# chlorophyll_analyzer_spectorometer.net
KiCad netlist of a schematic drawn in EAGLE
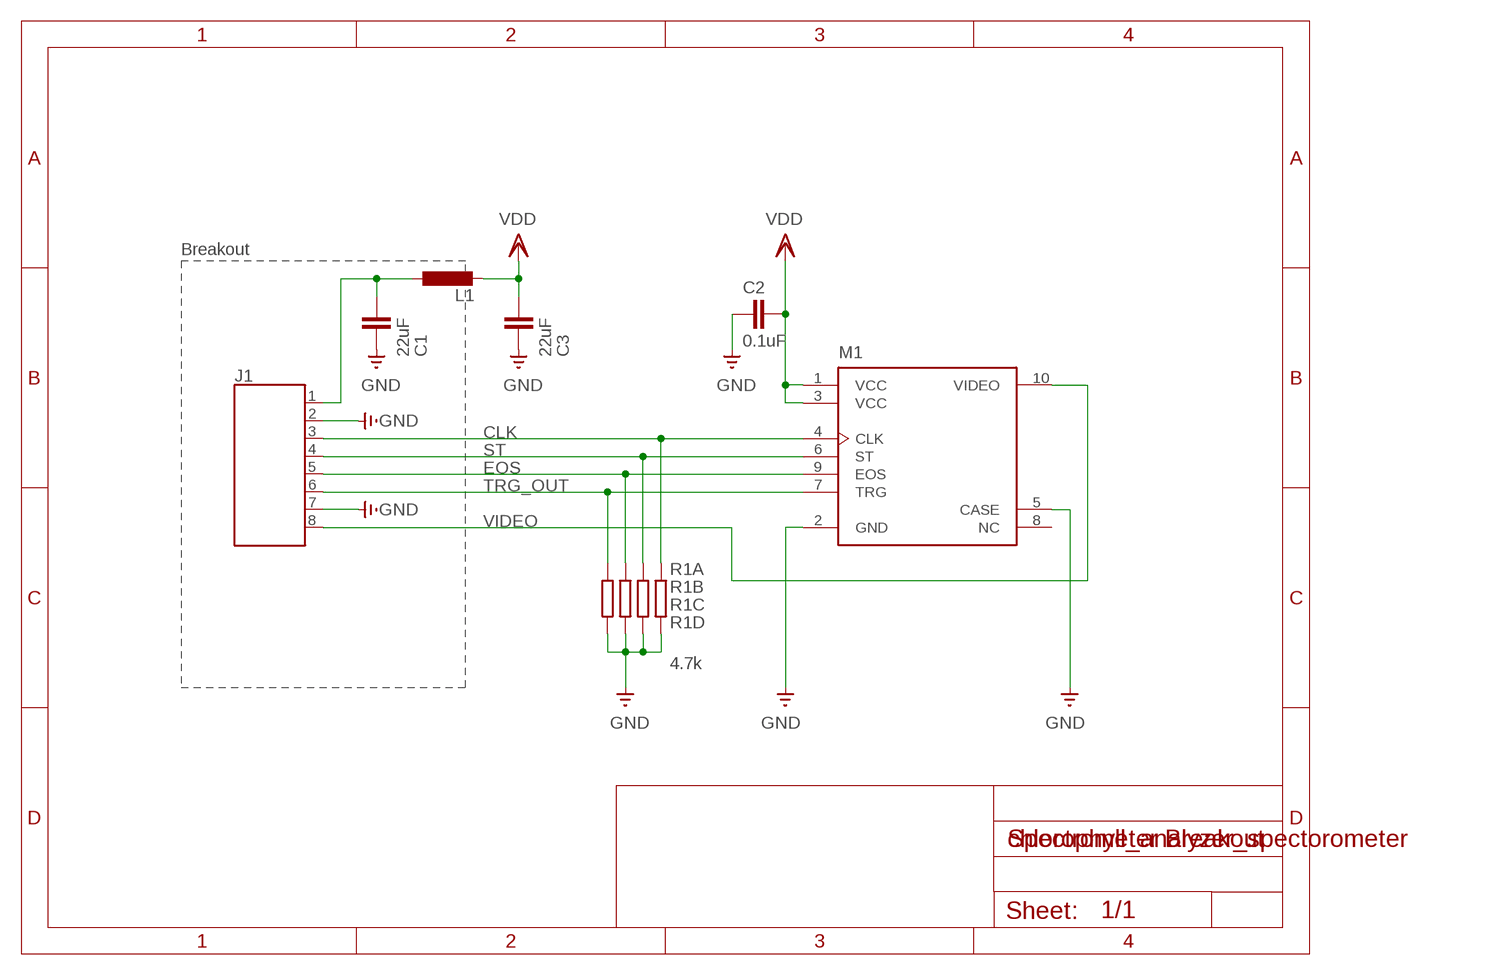
[diagram p0: schematic, sheet 1]

(export (version "E")
  (design (tool "Eeschema 10.0.6"))
  (components
    (comp (ref "C1")
      (value "22uF")
      (footprint "eagle-import:C0603K")
      (libsource (lib "eagle-import") (part "C-EUC0603K"))
    )
    (comp (ref "C2")
      (value "0.1uF")
      (footprint "eagle-import:C0603K")
      (libsource (lib "eagle-import") (part "C-EUC0603K"))
    )
    (comp (ref "C3")
      (value "22uF")
      (footprint "eagle-import:C0603K")
      (libsource (lib "eagle-import") (part "C-EUC0603K"))
    )
    (comp (ref "J1")
      (value "687108183722")
      (footprint "eagle-import:687108183722")
      (libsource (lib "eagle-import") (part "687108183722"))
    )
    (comp (ref "L1")
      (value "INDUCOR1608")
      (footprint "eagle-import:SMD1608")
      (libsource (lib "eagle-import") (part "INDUCOR1608"))
    )
    (comp (ref "M1")
      (value "C12880MA")
      (footprint "eagle-import:C12880MA")
      (libsource (lib "eagle-import") (part "C12880MA"))
    )
    (comp (ref "R1")
      (value "4.7k")
      (footprint "eagle-import:RESCAXS80P320X160X60-8N")
      (libsource (lib "eagle-import") (part "RESISTOR_ARRY1206"))
    )
  )
  (nets
    (net (code "1") (name "/CLK") (class "Default")
      (node (ref "J1") (pin "3") (pinfunction "6_3") (pintype "passive"))
      (node (ref "M1") (pin "4") (pinfunction "CLK_4") (pintype "input"))
      (node (ref "R1") (pin "5") (pinfunction "2_5") (pintype "passive"))
    )
    (net (code "2") (name "/EOS") (class "Default")
      (node (ref "J1") (pin "5") (pinfunction "4_5") (pintype "passive"))
      (node (ref "M1") (pin "9") (pinfunction "EOS_9") (pintype "output"))
      (node (ref "R1") (pin "7") (pinfunction "2_7") (pintype "passive"))
    )
    (net (code "3") (name "/ST") (class "Default")
      (node (ref "J1") (pin "4") (pinfunction "5_4") (pintype "passive"))
      (node (ref "M1") (pin "6") (pinfunction "ST_6") (pintype "input"))
      (node (ref "R1") (pin "6") (pinfunction "2_6") (pintype "passive"))
    )
    (net (code "4") (name "/TRG_OUT") (class "Default")
      (node (ref "J1") (pin "6") (pinfunction "3_6") (pintype "passive"))
      (node (ref "M1") (pin "7") (pinfunction "TRG_7") (pintype "output"))
      (node (ref "R1") (pin "8") (pinfunction "2_8") (pintype "passive"))
    )
    (net (code "5") (name "/VIDEO") (class "Default")
      (node (ref "J1") (pin "8") (pinfunction "1_8") (pintype "passive"))
      (node (ref "M1") (pin "10") (pinfunction "VIDEO_10") (pintype "output"))
    )
    (net (code "6") (name "GND") (class "Default")
      (node (ref "C1") (pin "2") (pinfunction "2_2") (pintype "passive"))
      (node (ref "C2") (pin "2") (pinfunction "2_2") (pintype "passive"))
      (node (ref "C3") (pin "2") (pinfunction "2_2") (pintype "passive"))
      (node (ref "J1") (pin "2") (pinfunction "7_2") (pintype "passive"))
      (node (ref "J1") (pin "7") (pinfunction "2_7") (pintype "passive"))
      (node (ref "M1") (pin "2") (pinfunction "GND_2") (pintype "power_in"))
      (node (ref "M1") (pin "5") (pinfunction "CASE_5") (pintype "passive"))
      (node (ref "R1") (pin "1") (pinfunction "1_1") (pintype "passive"))
      (node (ref "R1") (pin "2") (pinfunction "1_2") (pintype "passive"))
      (node (ref "R1") (pin "3") (pinfunction "1_3") (pintype "passive"))
      (node (ref "R1") (pin "4") (pinfunction "1_4") (pintype "passive"))
    )
    (net (code "7") (name "Net-(J1-8)") (class "Default")
      (node (ref "C1") (pin "1") (pinfunction "1_1") (pintype "passive"))
      (node (ref "J1") (pin "1") (pinfunction "8_1") (pintype "passive"))
      (node (ref "L1") (pin "1") (pinfunction "1_1") (pintype "passive"))
    )
    (net (code "8") (name "VDD") (class "Default")
      (node (ref "C2") (pin "1") (pinfunction "1_1") (pintype "passive"))
      (node (ref "C3") (pin "1") (pinfunction "1_1") (pintype "passive"))
      (node (ref "L1") (pin "2") (pinfunction "2_2") (pintype "passive"))
      (node (ref "M1") (pin "1") (pinfunction "VCC_1") (pintype "power_in"))
      (node (ref "M1") (pin "3") (pinfunction "VCC_3") (pintype "power_in"))
    )
    (net (code "9") (name "unconnected-(M1-NC-Pad8)") (class "Default")
      (node (ref "M1") (pin "8") (pinfunction "NC_8") (pintype "no_connect"))
    )
  )
)
